# simplefocmini_2024-04-26.net
KiCad netlist of a schematic drawn in Altium Designer
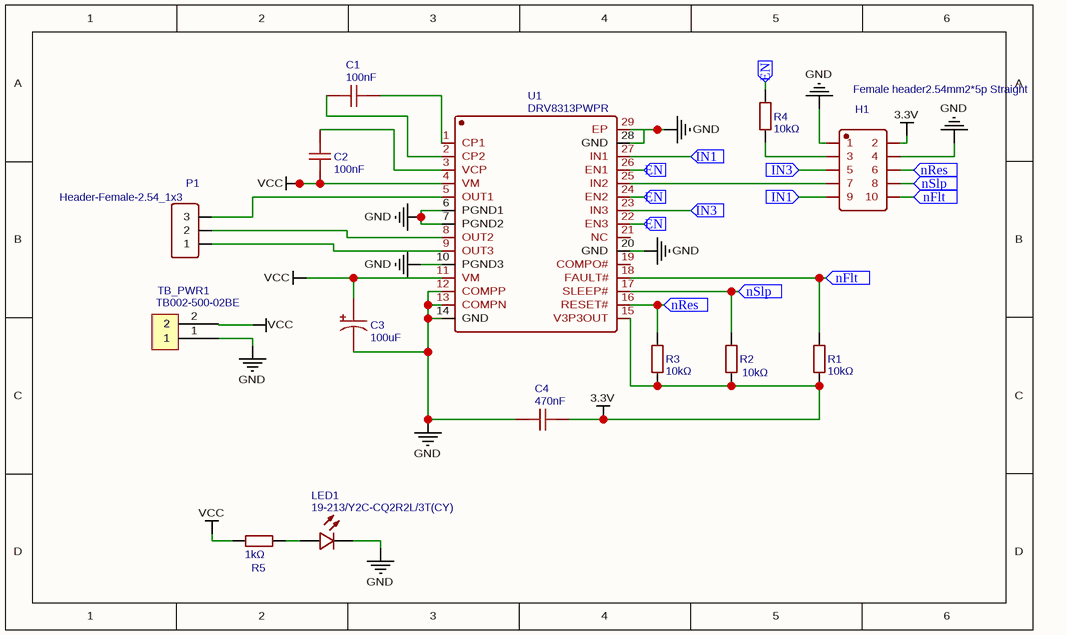
[diagram p0: simplefocmini_2024-04-26.schdoc]

(export (version "E")
  (design (tool "Eeschema 10.0.6"))
  (components
    (comp (ref "C1")
      (value "100nF")
      (fields (field (name "MANUFACTURER") "SAMSUNG") (field (name "MANUFACTURER PART") "CL10B104KB8NNNC"))
      (libsource (lib "altium-import") (part "root_0_100nF_"))
    )
    (comp (ref "C2")
      (value "100nF")
      (fields (field (name "MANUFACTURER") "SAMSUNG") (field (name "MANUFACTURER PART") "CL10B104KB8NNNC"))
      (libsource (lib "altium-import") (part "root_1_100nF_"))
    )
    (comp (ref "C3")
      (value "100uF")
      (fields
        (field (name "MANUFACTURER") "Vertical Technology")
        (field (name "MANUFACTURER PART") "VT1V101M-CRE77")
        (field (name "CONTRIBUTOR") "LCSC")
      )
      (libsource (lib "altium-import") (part "root_0_100uF_"))
    )
    (comp (ref "C4")
      (value "470nF")
      (fields
        (field (name "MANUFACTURER") "YAGEO")
        (field (name "MANUFACTURER PART") "CC0603ZRY5V6BB474")
        (field (name "CONTRIBUTOR") "LCSC")
      )
      (libsource (lib "altium-import") (part "root_0_470nF_"))
    )
    (comp (ref "H1")
      (value "Female header2.54mm2*5p Straight")
      (fields (field (name "MANUFACTURER") "ReliaPro"))
      (libsource (lib "altium-import") (part "root_0_Female header2.54mm2*5p Straight_"))
    )
    (comp (ref "LED1")
      (value "19-213/Y2C-CQ2R2L/3T(CY)")
      (fields (field (name "MANUFACTURER") "EVERLIGHT"))
      (libsource (lib "altium-import") (part "root_0_19-213/Y2C-CQ2R2L/3T(CY)_"))
    )
    (comp (ref "P1")
      (value "Header-Female-2.54_1x3")
      (fields (field (name "MANUFACTURER") "Boom Precision Elec"))
      (libsource (lib "altium-import") (part "root_2_Header-Female-2.54_1x3_"))
    )
    (comp (ref "R1")
      (value "10kΩ")
      (fields (field (name "MANUFACTURER") "UniOhm") (field (name "MANUFACTURER PART") "0603WAF4701T5E"))
      (libsource (lib "altium-import") (part "root_1_10kΩ_"))
    )
    (comp (ref "R2")
      (value "10kΩ")
      (fields (field (name "MANUFACTURER") "UniOhm") (field (name "MANUFACTURER PART") "0603WAF4701T5E"))
      (libsource (lib "altium-import") (part "root_1_10kΩ_"))
    )
    (comp (ref "R3")
      (value "10kΩ")
      (fields (field (name "MANUFACTURER") "UniOhm") (field (name "MANUFACTURER PART") "0603WAF4701T5E"))
      (libsource (lib "altium-import") (part "root_1_10kΩ_"))
    )
    (comp (ref "R4")
      (value "10kΩ")
      (fields (field (name "MANUFACTURER") "UniOhm") (field (name "MANUFACTURER PART") "0603WAF4701T5E"))
      (libsource (lib "altium-import") (part "root_1_10kΩ_"))
    )
    (comp (ref "R5")
      (value "1kΩ")
      (fields (field (name "MANUFACTURER") "UniOhm") (field (name "MANUFACTURER PART") "0603WAF4701T5E"))
      (libsource (lib "altium-import") (part "root_0_1kΩ_"))
    )
    (comp (ref "TB_PWR1")
      (value "TB002-500-02BE")
      (fields (field (name "CONTRIBUTOR") "the.skuric"))
      (libsource (lib "altium-import") (part "root_0_TB002-500-02BE_"))
    )
    (comp (ref "U1")
      (value "DRV8313PWPR")
      (fields (field (name "MANUFACTURER") "Texas Instruments") (field (name "CONTRIBUTOR") "LCSC"))
      (libsource (lib "altium-import") (part "root_0_DRV8313PWPR_"))
    )
  )
  (nets
    (net (code "1") (name "/EN") (class "Default")
      (node (ref "R4") (pin "2") (pinfunction "2_2") (pintype "passive"))
      (node (ref "U1") (pin "22") (pinfunction "EN3_22") (pintype "passive"))
      (node (ref "U1") (pin "24") (pinfunction "EN2_24") (pintype "passive"))
      (node (ref "U1") (pin "26") (pinfunction "EN1_26") (pintype "passive"))
    )
    (net (code "2") (name "/IN1") (class "Default")
      (node (ref "H1") (pin "9") (pinfunction "9_9") (pintype "passive"))
      (node (ref "U1") (pin "27") (pinfunction "IN1_27") (pintype "passive"))
    )
    (net (code "3") (name "/IN3") (class "Default")
      (node (ref "H1") (pin "5") (pinfunction "5_5") (pintype "passive"))
      (node (ref "U1") (pin "23") (pinfunction "IN3_23") (pintype "passive"))
    )
    (net (code "4") (name "/nFlt") (class "Default")
      (node (ref "H1") (pin "10") (pinfunction "10_10") (pintype "passive"))
      (node (ref "R1") (pin "2") (pinfunction "2_2") (pintype "passive"))
      (node (ref "U1") (pin "18") (pinfunction "FAULT#_18") (pintype "passive"))
    )
    (net (code "5") (name "/nRes") (class "Default")
      (node (ref "H1") (pin "6") (pinfunction "6_6") (pintype "passive"))
      (node (ref "R3") (pin "2") (pinfunction "2_2") (pintype "passive"))
      (node (ref "U1") (pin "16") (pinfunction "RESET#_16") (pintype "passive"))
    )
    (net (code "6") (name "/nSlp") (class "Default")
      (node (ref "H1") (pin "8") (pinfunction "8_8") (pintype "passive"))
      (node (ref "R2") (pin "2") (pinfunction "2_2") (pintype "passive"))
      (node (ref "U1") (pin "17") (pinfunction "SLEEP#_17") (pintype "passive"))
    )
    (net (code "7") (name "3.3V") (class "Default")
      (node (ref "C4") (pin "2") (pinfunction "2_2") (pintype "passive"))
      (node (ref "H1") (pin "2") (pinfunction "2_2") (pintype "passive"))
      (node (ref "R1") (pin "1") (pinfunction "1_1") (pintype "passive"))
      (node (ref "R2") (pin "1") (pinfunction "1_1") (pintype "passive"))
      (node (ref "R3") (pin "1") (pinfunction "1_1") (pintype "passive"))
      (node (ref "U1") (pin "15") (pinfunction "V3P3OUT_15") (pintype "passive"))
    )
    (net (code "8") (name "GND") (class "Default")
      (node (ref "C3") (pin "2") (pinfunction "2_2") (pintype "passive"))
      (node (ref "C4") (pin "1") (pinfunction "1_1") (pintype "passive"))
      (node (ref "H1") (pin "1") (pinfunction "1_1") (pintype "passive"))
      (node (ref "H1") (pin "4") (pinfunction "4_4") (pintype "passive"))
      (node (ref "LED1") (pin "2") (pinfunction "C_2") (pintype "passive"))
      (node (ref "TB_PWR1") (pin "1") (pinfunction "1_1") (pintype "passive"))
      (node (ref "U1") (pin "10") (pinfunction "PGND3_10") (pintype "passive"))
      (node (ref "U1") (pin "12") (pinfunction "COMPP_12") (pintype "passive"))
      (node (ref "U1") (pin "13") (pinfunction "COMPN_13") (pintype "passive"))
      (node (ref "U1") (pin "14") (pinfunction "GND_14") (pintype "passive"))
      (node (ref "U1") (pin "20") (pinfunction "GND_20") (pintype "passive"))
      (node (ref "U1") (pin "28") (pinfunction "GND_28") (pintype "passive"))
      (node (ref "U1") (pin "29") (pinfunction "EP_29") (pintype "passive"))
      (node (ref "U1") (pin "6") (pinfunction "PGND1_6") (pintype "passive"))
      (node (ref "U1") (pin "7") (pinfunction "PGND2_7") (pintype "passive"))
    )
    (net (code "9") (name "Net-(H1-Pad3)") (class "Default")
      (node (ref "H1") (pin "3") (pinfunction "3_3") (pintype "passive"))
      (node (ref "R4") (pin "1") (pinfunction "1_1") (pintype "passive"))
    )
    (net (code "10") (name "Net-(LED1-A)") (class "Default")
      (node (ref "LED1") (pin "1") (pinfunction "A_1") (pintype "passive"))
      (node (ref "R5") (pin "2") (pinfunction "2_2") (pintype "passive"))
    )
    (net (code "11") (name "Net-(U1-CP1)") (class "Default")
      (node (ref "C1") (pin "2") (pinfunction "2_2") (pintype "passive"))
      (node (ref "U1") (pin "1") (pinfunction "CP1_1") (pintype "passive"))
    )
    (net (code "12") (name "Net-(U1-CP2)") (class "Default")
      (node (ref "C1") (pin "1") (pinfunction "1_1") (pintype "passive"))
      (node (ref "U1") (pin "2") (pinfunction "CP2_2") (pintype "passive"))
    )
    (net (code "13") (name "Net-(U1-IN2)") (class "Default")
      (node (ref "H1") (pin "7") (pinfunction "7_7") (pintype "passive"))
      (node (ref "U1") (pin "25") (pinfunction "IN2_25") (pintype "passive"))
    )
    (net (code "14") (name "Net-(U1-OUT1)") (class "Default")
      (node (ref "P1") (pin "3") (pinfunction "3_3") (pintype "passive"))
      (node (ref "U1") (pin "5") (pinfunction "OUT1_5") (pintype "passive"))
    )
    (net (code "15") (name "Net-(U1-OUT2)") (class "Default")
      (node (ref "P1") (pin "2") (pinfunction "2_2") (pintype "passive"))
      (node (ref "U1") (pin "8") (pinfunction "OUT2_8") (pintype "passive"))
    )
    (net (code "16") (name "Net-(U1-OUT3)") (class "Default")
      (node (ref "P1") (pin "1") (pinfunction "1_1") (pintype "passive"))
      (node (ref "U1") (pin "9") (pinfunction "OUT3_9") (pintype "passive"))
    )
    (net (code "17") (name "Net-(U1-VCP)") (class "Default")
      (node (ref "C2") (pin "2") (pinfunction "2_2") (pintype "passive"))
      (node (ref "U1") (pin "3") (pinfunction "VCP_3") (pintype "passive"))
    )
    (net (code "18") (name "VCC") (class "Default")
      (node (ref "C2") (pin "1") (pinfunction "1_1") (pintype "passive"))
      (node (ref "C3") (pin "1") (pinfunction "1_1") (pintype "passive"))
      (node (ref "R5") (pin "1") (pinfunction "1_1") (pintype "passive"))
      (node (ref "TB_PWR1") (pin "2") (pinfunction "2_2") (pintype "passive"))
      (node (ref "U1") (pin "11") (pinfunction "VM_11") (pintype "passive"))
      (node (ref "U1") (pin "4") (pinfunction "VM_4") (pintype "passive"))
    )
    (net (code "19") (name "unconnected-(U1-COMPO#-Pad19)") (class "Default")
      (node (ref "U1") (pin "19") (pinfunction "COMPO#_19") (pintype "passive"))
    )
    (net (code "20") (name "unconnected-(U1-NC-Pad21)") (class "Default")
      (node (ref "U1") (pin "21") (pinfunction "NC_21") (pintype "passive"))
    )
  )
)
